# testboard_chip1_package.net
KiCad netlist of a schematic drawn in Altium Designer
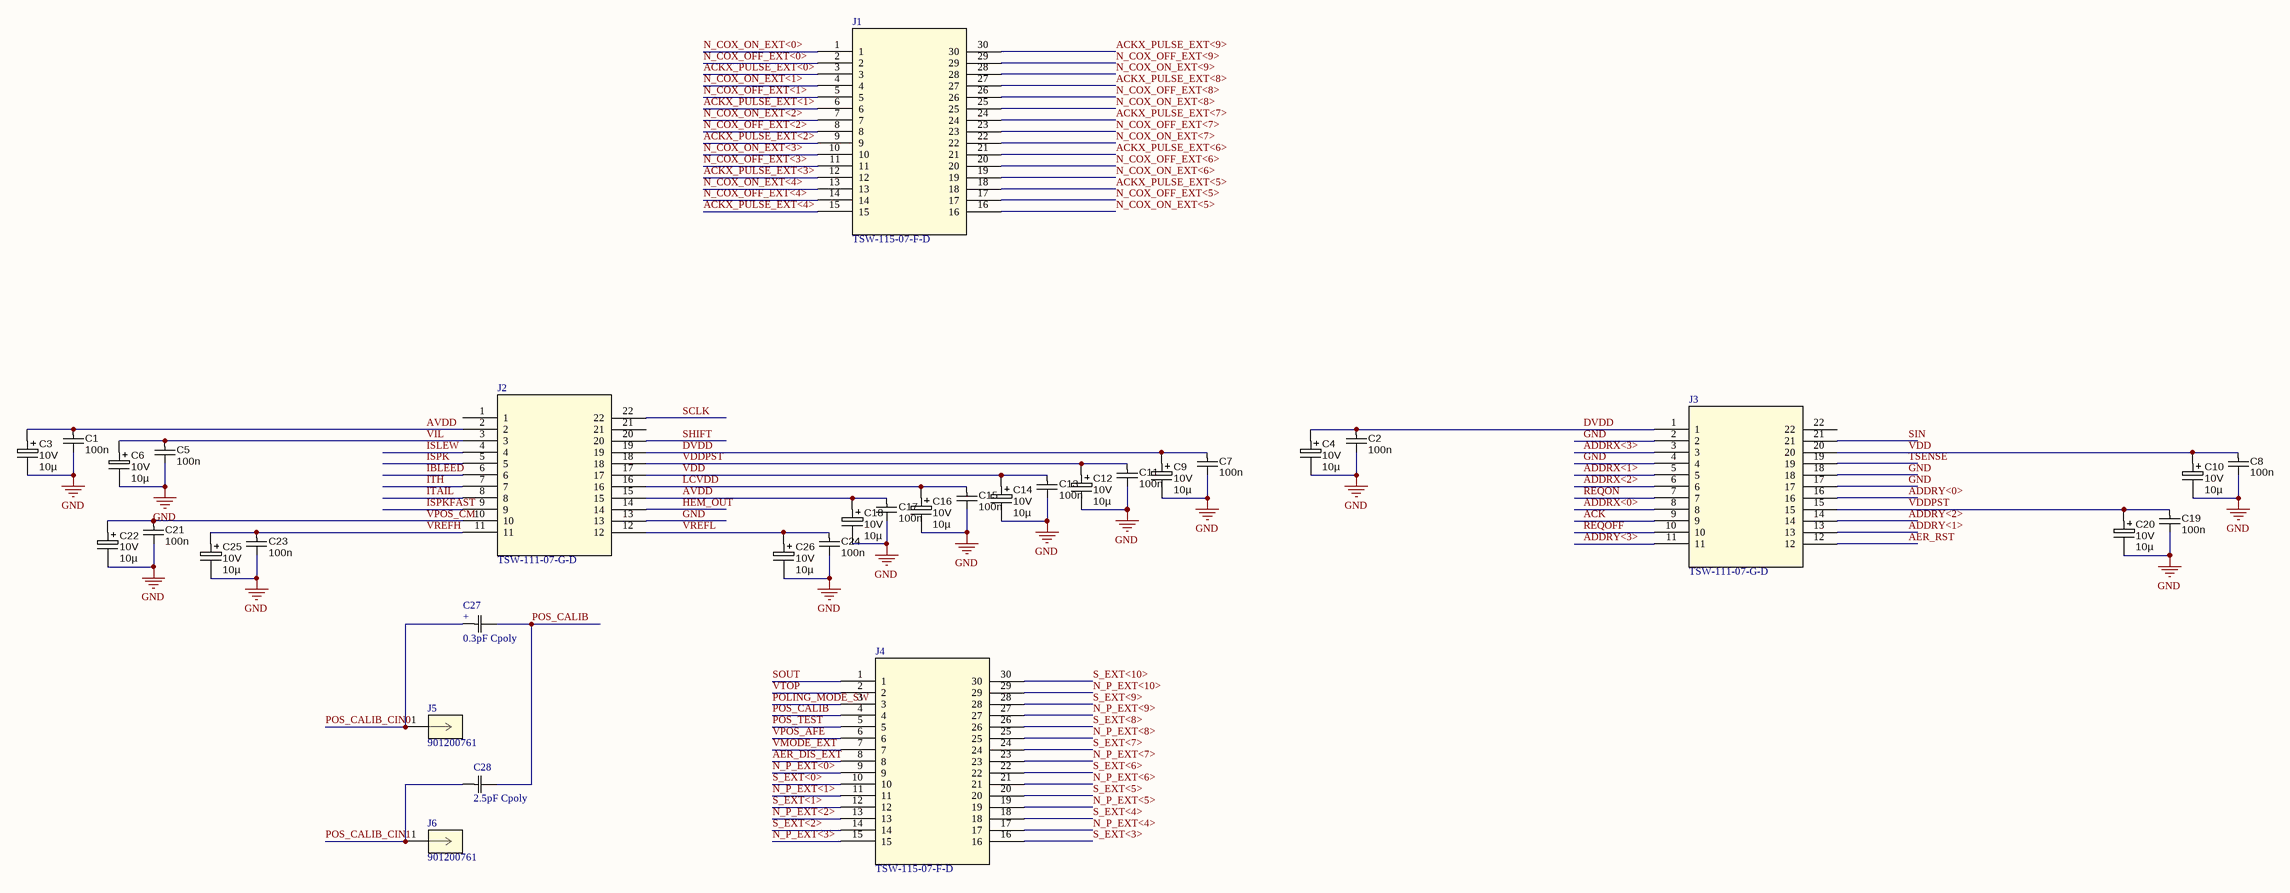
[diagram p0: testboard_chip1_package.SchDoc]

(export (version "E")
  (design (tool "Eeschema 10.0.6"))
  (components
    (comp (ref "C1")
      (value "100n")
      (footprint "CAPC1608N")
      (description "Capacitor SMD Cer 100nF 10% 50V X7R 0603")
      (fields (field (name "TOLERANCE") "±10%") (field (name "Comment") "approved sub OK"))
      (libsource (lib "PBL - Capacitors") (part "CAPC_100n_0603"))
    )
    (comp (ref "C2")
      (value "100n")
      (footprint "CAPC1608N")
      (description "Capacitor SMD Cer 100nF 10% 50V X7R 0603")
      (fields (field (name "TOLERANCE") "±10%") (field (name "Comment") "approved sub OK"))
      (libsource (lib "PBL - Capacitors") (part "CAPC_100n_0603"))
    )
    (comp (ref "C3")
      (value "10µ")
      (footprint "CAPMP2012X150USR")
      (description "Capacitor SMD Tantalum 10uF 20% 10V 0805")
      (fields (field (name "TOLERANCE") "±20%") (field (name "RATINGS") "10V"))
      (libsource (lib "PBL - Capacitors") (part "CAPT_10u_0805_10V"))
    )
    (comp (ref "C4")
      (value "10µ")
      (footprint "CAPMP2012X150USR")
      (description "Capacitor SMD Tantalum 10uF 20% 10V 0805")
      (fields (field (name "TOLERANCE") "±20%") (field (name "RATINGS") "10V"))
      (libsource (lib "PBL - Capacitors") (part "CAPT_10u_0805_10V"))
    )
    (comp (ref "C5")
      (value "100n")
      (footprint "CAPC1608N")
      (description "Capacitor SMD Cer 100nF 10% 50V X7R 0603")
      (fields (field (name "TOLERANCE") "±10%") (field (name "Comment") "approved sub OK"))
      (libsource (lib "PBL - Capacitors") (part "CAPC_100n_0603"))
    )
    (comp (ref "C6")
      (value "10µ")
      (footprint "CAPMP2012X150USR")
      (description "Capacitor SMD Tantalum 10uF 20% 10V 0805")
      (fields (field (name "TOLERANCE") "±20%") (field (name "RATINGS") "10V"))
      (libsource (lib "PBL - Capacitors") (part "CAPT_10u_0805_10V"))
    )
    (comp (ref "C7")
      (value "100n")
      (footprint "CAPC1608N")
      (description "Capacitor SMD Cer 100nF 10% 50V X7R 0603")
      (fields (field (name "TOLERANCE") "±10%") (field (name "Comment") "approved sub OK"))
      (libsource (lib "PBL - Capacitors") (part "CAPC_100n_0603"))
    )
    (comp (ref "C8")
      (value "100n")
      (footprint "CAPC1608N")
      (description "Capacitor SMD Cer 100nF 10% 50V X7R 0603")
      (fields (field (name "TOLERANCE") "±10%") (field (name "Comment") "approved sub OK"))
      (libsource (lib "PBL - Capacitors") (part "CAPC_100n_0603"))
    )
    (comp (ref "C9")
      (value "10µ")
      (footprint "CAPMP2012X150USR")
      (description "Capacitor SMD Tantalum 10uF 20% 10V 0805")
      (fields (field (name "TOLERANCE") "±20%") (field (name "RATINGS") "10V"))
      (libsource (lib "PBL - Capacitors") (part "CAPT_10u_0805_10V"))
    )
    (comp (ref "C10")
      (value "10µ")
      (footprint "CAPMP2012X150USR")
      (description "Capacitor SMD Tantalum 10uF 20% 10V 0805")
      (fields (field (name "TOLERANCE") "±20%") (field (name "RATINGS") "10V"))
      (libsource (lib "PBL - Capacitors") (part "CAPT_10u_0805_10V"))
    )
    (comp (ref "C11")
      (value "100n")
      (footprint "CAPC1608N")
      (description "Capacitor SMD Cer 100nF 10% 50V X7R 0603")
      (fields (field (name "TOLERANCE") "±10%") (field (name "Comment") "approved sub OK"))
      (libsource (lib "PBL - Capacitors") (part "CAPC_100n_0603"))
    )
    (comp (ref "C12")
      (value "10µ")
      (footprint "CAPMP2012X150USR")
      (description "Capacitor SMD Tantalum 10uF 20% 10V 0805")
      (fields (field (name "TOLERANCE") "±20%") (field (name "RATINGS") "10V"))
      (libsource (lib "PBL - Capacitors") (part "CAPT_10u_0805_10V"))
    )
    (comp (ref "C13")
      (value "100n")
      (footprint "CAPC1608N")
      (description "Capacitor SMD Cer 100nF 10% 50V X7R 0603")
      (fields (field (name "TOLERANCE") "±10%") (field (name "Comment") "approved sub OK"))
      (libsource (lib "PBL - Capacitors") (part "CAPC_100n_0603"))
    )
    (comp (ref "C14")
      (value "10µ")
      (footprint "CAPMP2012X150USR")
      (description "Capacitor SMD Tantalum 10uF 20% 10V 0805")
      (fields (field (name "TOLERANCE") "±20%") (field (name "RATINGS") "10V"))
      (libsource (lib "PBL - Capacitors") (part "CAPT_10u_0805_10V"))
    )
    (comp (ref "C15")
      (value "100n")
      (footprint "CAPC1608N")
      (description "Capacitor SMD Cer 100nF 10% 50V X7R 0603")
      (fields (field (name "TOLERANCE") "±10%") (field (name "Comment") "approved sub OK"))
      (libsource (lib "PBL - Capacitors") (part "CAPC_100n_0603"))
    )
    (comp (ref "C16")
      (value "10µ")
      (footprint "CAPMP2012X150USR")
      (description "Capacitor SMD Tantalum 10uF 20% 10V 0805")
      (fields (field (name "TOLERANCE") "±20%") (field (name "RATINGS") "10V"))
      (libsource (lib "PBL - Capacitors") (part "CAPT_10u_0805_10V"))
    )
    (comp (ref "C17")
      (value "100n")
      (footprint "CAPC1608N")
      (description "Capacitor SMD Cer 100nF 10% 50V X7R 0603")
      (fields (field (name "TOLERANCE") "±10%") (field (name "Comment") "approved sub OK"))
      (libsource (lib "PBL - Capacitors") (part "CAPC_100n_0603"))
    )
    (comp (ref "C18")
      (value "10µ")
      (footprint "CAPMP2012X150USR")
      (description "Capacitor SMD Tantalum 10uF 20% 10V 0805")
      (fields (field (name "TOLERANCE") "±20%") (field (name "RATINGS") "10V"))
      (libsource (lib "PBL - Capacitors") (part "CAPT_10u_0805_10V"))
    )
    (comp (ref "C19")
      (value "100n")
      (footprint "CAPC1608N")
      (description "Capacitor SMD Cer 100nF 10% 50V X7R 0603")
      (fields (field (name "TOLERANCE") "±10%") (field (name "Comment") "approved sub OK"))
      (libsource (lib "PBL - Capacitors") (part "CAPC_100n_0603"))
    )
    (comp (ref "C20")
      (value "10µ")
      (footprint "CAPMP2012X150USR")
      (description "Capacitor SMD Tantalum 10uF 20% 10V 0805")
      (fields (field (name "TOLERANCE") "±20%") (field (name "RATINGS") "10V"))
      (libsource (lib "PBL - Capacitors") (part "CAPT_10u_0805_10V"))
    )
    (comp (ref "C21")
      (value "100n")
      (footprint "CAPC1608N")
      (description "Capacitor SMD Cer 100nF 10% 50V X7R 0603")
      (fields (field (name "TOLERANCE") "±10%") (field (name "Comment") "approved sub OK"))
      (libsource (lib "PBL - Capacitors") (part "CAPC_100n_0603"))
    )
    (comp (ref "C22")
      (value "10µ")
      (footprint "CAPMP2012X150USR")
      (description "Capacitor SMD Tantalum 10uF 20% 10V 0805")
      (fields (field (name "TOLERANCE") "±20%") (field (name "RATINGS") "10V"))
      (libsource (lib "PBL - Capacitors") (part "CAPT_10u_0805_10V"))
    )
    (comp (ref "C23")
      (value "100n")
      (footprint "CAPC1608N")
      (description "Capacitor SMD Cer 100nF 10% 50V X7R 0603")
      (fields (field (name "TOLERANCE") "±10%") (field (name "Comment") "approved sub OK"))
      (libsource (lib "PBL - Capacitors") (part "CAPC_100n_0603"))
    )
    (comp (ref "C24")
      (value "100n")
      (footprint "CAPC1608N")
      (description "Capacitor SMD Cer 100nF 10% 50V X7R 0603")
      (fields (field (name "TOLERANCE") "±10%") (field (name "Comment") "approved sub OK"))
      (libsource (lib "PBL - Capacitors") (part "CAPC_100n_0603"))
    )
    (comp (ref "C25")
      (value "10µ")
      (footprint "CAPMP2012X150USR")
      (description "Capacitor SMD Tantalum 10uF 20% 10V 0805")
      (fields (field (name "TOLERANCE") "±20%") (field (name "RATINGS") "10V"))
      (libsource (lib "PBL - Capacitors") (part "CAPT_10u_0805_10V"))
    )
    (comp (ref "C26")
      (value "10µ")
      (footprint "CAPMP2012X150USR")
      (description "Capacitor SMD Tantalum 10uF 20% 10V 0805")
      (fields (field (name "TOLERANCE") "±20%") (field (name "RATINGS") "10V"))
      (libsource (lib "PBL - Capacitors") (part "CAPT_10u_0805_10V"))
    )
    (comp (ref "C27")
      (value "0.3pF Cpoly")
      (footprint "CAP_0603_AVX")
      (description "No Description Available")
      (fields
        (field (name "MANUFACTURER_PART_NUMBER") "06035J0R3PBSTR")
        (field (name "COPYRIGHT") "Copyright (C) 2022 Ultra Librarian. All rights reserved.")
      )
      (libsource (lib "06035J0R3PBSTR") (part "06035J0R3PBSTR"))
    )
    (comp (ref "C28")
      (value "2.5pF Cpoly")
      (footprint "CAPC17090_87N_KEM")
      (description "No Description Available")
      (fields
        (field (name "MANUFACTURER_PART_NUMBER") "CBR06C259B5GAC")
        (field (name "COPYRIGHT") "Copyright (C) 2022 Ultra Librarian. All rights reserved.")
      )
      (libsource (lib "CBR06C259B5GAC") (part "CBR06C259B5GAC"))
    )
    (comp (ref "J1")
      (value "TSW-115-07-F-D")
      (footprint "TSW-115-07-G-D_SAI")
      (description "No Description Available")
      (fields (field (name "COPYRIGHT") "Copyright (C) 2022 Ultra Librarian. All rights reserved."))
      (libsource (lib "TSW-115-07-F-D") (part "TSW-115-07-F-D"))
    )
    (comp (ref "J2")
      (value "TSW-111-07-G-D")
      (footprint "TSW-111-07-G-D_SAI")
      (description "No Description Available")
      (fields (field (name "COPYRIGHT") "Copyright (C) 2022 Ultra Librarian. All rights reserved."))
      (libsource (lib "TSW-111-07-G-D") (part "TSW-111-07-G-D"))
    )
    (comp (ref "J3")
      (value "TSW-111-07-G-D")
      (footprint "TSW-111-07-G-D_SAI")
      (description "No Description Available")
      (fields (field (name "COPYRIGHT") "Copyright (C) 2022 Ultra Librarian. All rights reserved."))
      (libsource (lib "TSW-111-07-G-D") (part "TSW-111-07-G-D"))
    )
    (comp (ref "J4")
      (value "TSW-115-07-F-D")
      (footprint "TSW-115-07-G-D_SAI")
      (description "No Description Available")
      (fields (field (name "COPYRIGHT") "Copyright (C) 2022 Ultra Librarian. All rights reserved."))
      (libsource (lib "TSW-115-07-F-D") (part "TSW-115-07-F-D"))
    )
    (comp (ref "J5")
      (value "901200761")
      (footprint "CONN_90120-0761_MOL")
      (description "No Description Available")
      (fields (field (name "COPYRIGHT") "Copyright (C) 2022 Ultra Librarian. All rights reserved."))
      (libsource (lib "901200761") (part "901200761"))
    )
    (comp (ref "J6")
      (value "901200761")
      (footprint "CONN_90120-0761_MOL")
      (description "No Description Available")
      (fields (field (name "COPYRIGHT") "Copyright (C) 2022 Ultra Librarian. All rights reserved."))
      (libsource (lib "901200761") (part "901200761"))
    )
  )
  (nets
    (net (code "1") (name "/ACK") (class "Default")
      (node (ref "J3") (pin "9") (pinfunction "9_9") (pintype "passive"))
    )
    (net (code "2") (name "/ACKX_PULSE_EXT<0>") (class "Default")
      (node (ref "J1") (pin "3") (pinfunction "3_3") (pintype "passive"))
    )
    (net (code "3") (name "/ACKX_PULSE_EXT<1>") (class "Default")
      (node (ref "J1") (pin "6") (pinfunction "6_6") (pintype "passive"))
    )
    (net (code "4") (name "/ACKX_PULSE_EXT<2>") (class "Default")
      (node (ref "J1") (pin "9") (pinfunction "9_9") (pintype "passive"))
    )
    (net (code "5") (name "/ACKX_PULSE_EXT<3>") (class "Default")
      (node (ref "J1") (pin "12") (pinfunction "12_12") (pintype "passive"))
    )
    (net (code "6") (name "/ACKX_PULSE_EXT<4>") (class "Default")
      (node (ref "J1") (pin "15") (pinfunction "15_15") (pintype "passive"))
    )
    (net (code "7") (name "/ACKX_PULSE_EXT<5>") (class "Default")
      (node (ref "J1") (pin "18") (pinfunction "18_18") (pintype "passive"))
    )
    (net (code "8") (name "/ACKX_PULSE_EXT<6>") (class "Default")
      (node (ref "J1") (pin "21") (pinfunction "21_21") (pintype "passive"))
    )
    (net (code "9") (name "/ACKX_PULSE_EXT<7>") (class "Default")
      (node (ref "J1") (pin "24") (pinfunction "24_24") (pintype "passive"))
    )
    (net (code "10") (name "/ACKX_PULSE_EXT<8>") (class "Default")
      (node (ref "J1") (pin "27") (pinfunction "27_27") (pintype "passive"))
    )
    (net (code "11") (name "/ACKX_PULSE_EXT<9>") (class "Default")
      (node (ref "J1") (pin "30") (pinfunction "30_30") (pintype "passive"))
    )
    (net (code "12") (name "/ADDRX<0>") (class "Default")
      (node (ref "J3") (pin "8") (pinfunction "8_8") (pintype "passive"))
    )
    (net (code "13") (name "/ADDRX<1>") (class "Default")
      (node (ref "J3") (pin "5") (pinfunction "5_5") (pintype "passive"))
    )
    (net (code "14") (name "/ADDRX<2>") (class "Default")
      (node (ref "J3") (pin "6") (pinfunction "6_6") (pintype "passive"))
    )
    (net (code "15") (name "/ADDRX<3>") (class "Default")
      (node (ref "J3") (pin "3") (pinfunction "3_3") (pintype "passive"))
    )
    (net (code "16") (name "/ADDRY<0>") (class "Default")
      (node (ref "J3") (pin "16") (pinfunction "16_16") (pintype "passive"))
    )
    (net (code "17") (name "/ADDRY<1>") (class "Default")
      (node (ref "J3") (pin "13") (pinfunction "13_13") (pintype "passive"))
    )
    (net (code "18") (name "/ADDRY<2>") (class "Default")
      (node (ref "J3") (pin "14") (pinfunction "14_14") (pintype "passive"))
    )
    (net (code "19") (name "/ADDRY<3>") (class "Default")
      (node (ref "J3") (pin "11") (pinfunction "11_11") (pintype "passive"))
    )
    (net (code "20") (name "/AER_DIS_EXT") (class "Default")
      (node (ref "J4") (pin "8") (pinfunction "8_8") (pintype "passive"))
    )
    (net (code "21") (name "/AER_RST") (class "Default")
      (node (ref "J3") (pin "12") (pinfunction "12_12") (pintype "passive"))
    )
    (net (code "22") (name "/AVDD") (class "Default")
      (node (ref "C1") (pin "1") (pintype "passive"))
      (node (ref "C17") (pin "1") (pintype "passive"))
      (node (ref "C18") (pin "1") (pintype "passive"))
      (node (ref "C3") (pin "1") (pintype "passive"))
      (node (ref "J2") (pin "15") (pinfunction "15_15") (pintype "passive"))
      (node (ref "J2") (pin "2") (pinfunction "2_2") (pintype "passive"))
    )
    (net (code "23") (name "/DVDD") (class "Default")
      (node (ref "C2") (pin "1") (pintype "passive"))
      (node (ref "C4") (pin "1") (pintype "passive"))
      (node (ref "C7") (pin "1") (pintype "passive"))
      (node (ref "C9") (pin "1") (pintype "passive"))
      (node (ref "J2") (pin "19") (pinfunction "19_19") (pintype "passive"))
      (node (ref "J3") (pin "1") (pinfunction "1_1") (pintype "passive"))
    )
    (net (code "24") (name "/HEM_OUT") (class "Default")
      (node (ref "J2") (pin "14") (pinfunction "14_14") (pintype "passive"))
    )
    (net (code "25") (name "/IBLEED") (class "Default")
      (node (ref "J2") (pin "6") (pinfunction "6_6") (pintype "passive"))
    )
    (net (code "26") (name "/ISLEW") (class "Default")
      (node (ref "J2") (pin "4") (pinfunction "4_4") (pintype "passive"))
    )
    (net (code "27") (name "/ISPK") (class "Default")
      (node (ref "J2") (pin "5") (pinfunction "5_5") (pintype "passive"))
    )
    (net (code "28") (name "/ISPKFAST") (class "Default")
      (node (ref "J2") (pin "9") (pinfunction "9_9") (pintype "passive"))
    )
    (net (code "29") (name "/ITAIL") (class "Default")
      (node (ref "J2") (pin "8") (pinfunction "8_8") (pintype "passive"))
    )
    (net (code "30") (name "/ITH") (class "Default")
      (node (ref "J2") (pin "7") (pinfunction "7_7") (pintype "passive"))
    )
    (net (code "31") (name "/LCVDD") (class "Default")
      (node (ref "C15") (pin "1") (pintype "passive"))
      (node (ref "C16") (pin "1") (pintype "passive"))
      (node (ref "J2") (pin "16") (pinfunction "16_16") (pintype "passive"))
    )
    (net (code "32") (name "/N_COX_OFF_EXT<0>") (class "Default")
      (node (ref "J1") (pin "2") (pinfunction "2_2") (pintype "passive"))
    )
    (net (code "33") (name "/N_COX_OFF_EXT<1>") (class "Default")
      (node (ref "J1") (pin "5") (pinfunction "5_5") (pintype "passive"))
    )
    (net (code "34") (name "/N_COX_OFF_EXT<2>") (class "Default")
      (node (ref "J1") (pin "8") (pinfunction "8_8") (pintype "passive"))
    )
    (net (code "35") (name "/N_COX_OFF_EXT<3>") (class "Default")
      (node (ref "J1") (pin "11") (pinfunction "11_11") (pintype "passive"))
    )
    (net (code "36") (name "/N_COX_OFF_EXT<4>") (class "Default")
      (node (ref "J1") (pin "14") (pinfunction "14_14") (pintype "passive"))
    )
    (net (code "37") (name "/N_COX_OFF_EXT<5>") (class "Default")
      (node (ref "J1") (pin "17") (pinfunction "17_17") (pintype "passive"))
    )
    (net (code "38") (name "/N_COX_OFF_EXT<6>") (class "Default")
      (node (ref "J1") (pin "20") (pinfunction "20_20") (pintype "passive"))
    )
    (net (code "39") (name "/N_COX_OFF_EXT<7>") (class "Default")
      (node (ref "J1") (pin "23") (pinfunction "23_23") (pintype "passive"))
    )
    (net (code "40") (name "/N_COX_OFF_EXT<8>") (class "Default")
      (node (ref "J1") (pin "26") (pinfunction "26_26") (pintype "passive"))
    )
    (net (code "41") (name "/N_COX_OFF_EXT<9>") (class "Default")
      (node (ref "J1") (pin "29") (pinfunction "29_29") (pintype "passive"))
    )
    (net (code "42") (name "/N_COX_ON_EXT<0>") (class "Default")
      (node (ref "J1") (pin "1") (pinfunction "1_1") (pintype "passive"))
    )
    (net (code "43") (name "/N_COX_ON_EXT<1>") (class "Default")
      (node (ref "J1") (pin "4") (pinfunction "4_4") (pintype "passive"))
    )
    (net (code "44") (name "/N_COX_ON_EXT<2>") (class "Default")
      (node (ref "J1") (pin "7") (pinfunction "7_7") (pintype "passive"))
    )
    (net (code "45") (name "/N_COX_ON_EXT<3>") (class "Default")
      (node (ref "J1") (pin "10") (pinfunction "10_10") (pintype "passive"))
    )
    (net (code "46") (name "/N_COX_ON_EXT<4>") (class "Default")
      (node (ref "J1") (pin "13") (pinfunction "13_13") (pintype "passive"))
    )
    (net (code "47") (name "/N_COX_ON_EXT<5>") (class "Default")
      (node (ref "J1") (pin "16") (pinfunction "16_16") (pintype "passive"))
    )
    (net (code "48") (name "/N_COX_ON_EXT<6>") (class "Default")
      (node (ref "J1") (pin "19") (pinfunction "19_19") (pintype "passive"))
    )
    (net (code "49") (name "/N_COX_ON_EXT<7>") (class "Default")
      (node (ref "J1") (pin "22") (pinfunction "22_22") (pintype "passive"))
    )
    (net (code "50") (name "/N_COX_ON_EXT<8>") (class "Default")
      (node (ref "J1") (pin "25") (pinfunction "25_25") (pintype "passive"))
    )
    (net (code "51") (name "/N_COX_ON_EXT<9>") (class "Default")
      (node (ref "J1") (pin "28") (pinfunction "28_28") (pintype "passive"))
    )
    (net (code "52") (name "/N_P_EXT<0>") (class "Default")
      (node (ref "J4") (pin "9") (pinfunction "9_9") (pintype "passive"))
    )
    (net (code "53") (name "/N_P_EXT<1>") (class "Default")
      (node (ref "J4") (pin "11") (pinfunction "11_11") (pintype "passive"))
    )
    (net (code "54") (name "/N_P_EXT<2>") (class "Default")
      (node (ref "J4") (pin "13") (pinfunction "13_13") (pintype "passive"))
    )
    (net (code "55") (name "/N_P_EXT<3>") (class "Default")
      (node (ref "J4") (pin "15") (pinfunction "15_15") (pintype "passive"))
    )
    (net (code "56") (name "/N_P_EXT<4>") (class "Default")
      (node (ref "J4") (pin "17") (pinfunction "17_17") (pintype "passive"))
    )
    (net (code "57") (name "/N_P_EXT<5>") (class "Default")
      (node (ref "J4") (pin "19") (pinfunction "19_19") (pintype "passive"))
    )
    (net (code "58") (name "/N_P_EXT<6>") (class "Default")
      (node (ref "J4") (pin "21") (pinfunction "21_21") (pintype "passive"))
    )
    (net (code "59") (name "/N_P_EXT<7>") (class "Default")
      (node (ref "J4") (pin "23") (pinfunction "23_23") (pintype "passive"))
    )
    (net (code "60") (name "/N_P_EXT<8>") (class "Default")
      (node (ref "J4") (pin "25") (pinfunction "25_25") (pintype "passive"))
    )
    (net (code "61") (name "/N_P_EXT<9>") (class "Default")
      (node (ref "J4") (pin "27") (pinfunction "27_27") (pintype "passive"))
    )
    (net (code "62") (name "/N_P_EXT<10>") (class "Default")
      (node (ref "J4") (pin "29") (pinfunction "29_29") (pintype "passive"))
    )
    (net (code "63") (name "/POLING_MODE_SW") (class "Default")
      (node (ref "J4") (pin "3") (pinfunction "3_3") (pintype "passive"))
    )
    (net (code "64") (name "/POS_CALIB") (class "Default")
      (node (ref "C27") (pin "2") (pinfunction "2_2") (pintype "passive"))
      (node (ref "C28") (pin "2") (pinfunction "2_2") (pintype "passive"))
      (node (ref "J4") (pin "4") (pinfunction "4_4") (pintype "passive"))
    )
    (net (code "65") (name "/POS_CALIB_CIN0") (class "Default")
      (node (ref "C27") (pin "1") (pinfunction "1_1") (pintype "passive"))
      (node (ref "J5") (pin "1") (pinfunction "1_1") (pintype "passive"))
    )
    (net (code "66") (name "/POS_CALIB_CIN1") (class "Default")
      (node (ref "C28") (pin "1") (pinfunction "1_1") (pintype "passive"))
      (node (ref "J6") (pin "1") (pinfunction "1_1") (pintype "passive"))
    )
    (net (code "67") (name "/POS_TEST") (class "Default")
      (node (ref "J4") (pin "5") (pinfunction "5_5") (pintype "passive"))
    )
    (net (code "68") (name "/REQOFF") (class "Default")
      (node (ref "J3") (pin "10") (pinfunction "10_10") (pintype "passive"))
    )
    (net (code "69") (name "/REQON") (class "Default")
      (node (ref "J3") (pin "7") (pinfunction "7_7") (pintype "passive"))
    )
    (net (code "70") (name "/SCLK") (class "Default")
      (node (ref "J2") (pin "22") (pinfunction "22_22") (pintype "passive"))
    )
    (net (code "71") (name "/SHIFT") (class "Default")
      (node (ref "J2") (pin "20") (pinfunction "20_20") (pintype "passive"))
    )
    (net (code "72") (name "/SIN") (class "Default")
      (node (ref "J3") (pin "21") (pinfunction "21_21") (pintype "passive"))
    )
    (net (code "73") (name "/SOUT") (class "Default")
      (node (ref "J4") (pin "1") (pinfunction "1_1") (pintype "passive"))
    )
    (net (code "74") (name "/S_EXT<0>") (class "Default")
      (node (ref "J4") (pin "10") (pinfunction "10_10") (pintype "passive"))
    )
    (net (code "75") (name "/S_EXT<1>") (class "Default")
      (node (ref "J4") (pin "12") (pinfunction "12_12") (pintype "passive"))
    )
    (net (code "76") (name "/S_EXT<2>") (class "Default")
      (node (ref "J4") (pin "14") (pinfunction "14_14") (pintype "passive"))
    )
    (net (code "77") (name "/S_EXT<3>") (class "Default")
      (node (ref "J4") (pin "16") (pinfunction "16_16") (pintype "passive"))
    )
    (net (code "78") (name "/S_EXT<4>") (class "Default")
      (node (ref "J4") (pin "18") (pinfunction "18_18") (pintype "passive"))
    )
    (net (code "79") (name "/S_EXT<5>") (class "Default")
      (node (ref "J4") (pin "20") (pinfunction "20_20") (pintype "passive"))
    )
    (net (code "80") (name "/S_EXT<6>") (class "Default")
      (node (ref "J4") (pin "22") (pinfunction "22_22") (pintype "passive"))
    )
    (net (code "81") (name "/S_EXT<7>") (class "Default")
      (node (ref "J4") (pin "24") (pinfunction "24_24") (pintype "passive"))
    )
    (net (code "82") (name "/S_EXT<8>") (class "Default")
      (node (ref "J4") (pin "26") (pinfunction "26_26") (pintype "passive"))
    )
    (net (code "83") (name "/S_EXT<9>") (class "Default")
      (node (ref "J4") (pin "28") (pinfunction "28_28") (pintype "passive"))
    )
    (net (code "84") (name "/S_EXT<10>") (class "Default")
      (node (ref "J4") (pin "30") (pinfunction "30_30") (pintype "passive"))
    )
    (net (code "85") (name "/TSENSE") (class "Default")
      (node (ref "J3") (pin "19") (pinfunction "19_19") (pintype "passive"))
    )
    (net (code "86") (name "/VDD") (class "Default")
      (node (ref "C10") (pin "1") (pintype "passive"))
      (node (ref "C13") (pin "1") (pintype "passive"))
      (node (ref "C14") (pin "1") (pintype "passive"))
      (node (ref "C8") (pin "1") (pintype "passive"))
      (node (ref "J2") (pin "17") (pinfunction "17_17") (pintype "passive"))
      (node (ref "J3") (pin "20") (pinfunction "20_20") (pintype "passive"))
    )
    (net (code "87") (name "/VDDPST") (class "Default")
      (node (ref "C11") (pin "1") (pintype "passive"))
      (node (ref "C12") (pin "1") (pintype "passive"))
      (node (ref "C19") (pin "1") (pintype "passive"))
      (node (ref "C20") (pin "1") (pintype "passive"))
      (node (ref "J2") (pin "18") (pinfunction "18_18") (pintype "passive"))
      (node (ref "J3") (pin "15") (pinfunction "15_15") (pintype "passive"))
    )
    (net (code "88") (name "/VIL") (class "Default")
      (node (ref "C5") (pin "1") (pintype "passive"))
      (node (ref "C6") (pin "1") (pintype "passive"))
      (node (ref "J2") (pin "3") (pinfunction "3_3") (pintype "passive"))
    )
    (net (code "89") (name "/VMODE_EXT") (class "Default")
      (node (ref "J4") (pin "7") (pinfunction "7_7") (pintype "passive"))
    )
    (net (code "90") (name "/VPOS_AFE") (class "Default")
      (node (ref "J4") (pin "6") (pinfunction "6_6") (pintype "passive"))
    )
    (net (code "91") (name "/VPOS_CM") (class "Default")
      (node (ref "C21") (pin "1") (pintype "passive"))
      (node (ref "C22") (pin "1") (pintype "passive"))
      (node (ref "J2") (pin "10") (pinfunction "10_10") (pintype "passive"))
    )
    (net (code "92") (name "/VREFH") (class "Default")
      (node (ref "C23") (pin "1") (pintype "passive"))
      (node (ref "C25") (pin "1") (pintype "passive"))
      (node (ref "J2") (pin "11") (pinfunction "11_11") (pintype "passive"))
    )
    (net (code "93") (name "/VREFL") (class "Default")
      (node (ref "C24") (pin "1") (pintype "passive"))
      (node (ref "C26") (pin "1") (pintype "passive"))
      (node (ref "J2") (pin "12") (pinfunction "12_12") (pintype "passive"))
    )
    (net (code "94") (name "/VTOP") (class "Default")
      (node (ref "J4") (pin "2") (pinfunction "2_2") (pintype "passive"))
    )
    (net (code "95") (name "GND") (class "Default")
      (node (ref "C1") (pin "2") (pintype "passive"))
      (node (ref "C10") (pin "2") (pintype "passive"))
      (node (ref "C11") (pin "2") (pintype "passive"))
      (node (ref "C12") (pin "2") (pintype "passive"))
      (node (ref "C13") (pin "2") (pintype "passive"))
      (node (ref "C14") (pin "2") (pintype "passive"))
      (node (ref "C15") (pin "2") (pintype "passive"))
      (node (ref "C16") (pin "2") (pintype "passive"))
      (node (ref "C17") (pin "2") (pintype "passive"))
      (node (ref "C18") (pin "2") (pintype "passive"))
      (node (ref "C19") (pin "2") (pintype "passive"))
      (node (ref "C2") (pin "2") (pintype "passive"))
      (node (ref "C20") (pin "2") (pintype "passive"))
      (node (ref "C21") (pin "2") (pintype "passive"))
      (node (ref "C22") (pin "2") (pintype "passive"))
      (node (ref "C23") (pin "2") (pintype "passive"))
      (node (ref "C24") (pin "2") (pintype "passive"))
      (node (ref "C25") (pin "2") (pintype "passive"))
      (node (ref "C26") (pin "2") (pintype "passive"))
      (node (ref "C3") (pin "2") (pintype "passive"))
      (node (ref "C4") (pin "2") (pintype "passive"))
      (node (ref "C5") (pin "2") (pintype "passive"))
      (node (ref "C6") (pin "2") (pintype "passive"))
      (node (ref "C7") (pin "2") (pintype "passive"))
      (node (ref "C8") (pin "2") (pintype "passive"))
      (node (ref "C9") (pin "2") (pintype "passive"))
      (node (ref "J2") (pin "13") (pinfunction "13_13") (pintype "passive"))
      (node (ref "J3") (pin "17") (pinfunction "17_17") (pintype "passive"))
      (node (ref "J3") (pin "18") (pinfunction "18_18") (pintype "passive"))
      (node (ref "J3") (pin "2") (pinfunction "2_2") (pintype "passive"))
      (node (ref "J3") (pin "4") (pinfunction "4_4") (pintype "passive"))
    )
    (net (code "96") (name "unconnected-(J2-Pad1)") (class "Default")
      (node (ref "J2") (pin "1") (pinfunction "1_1") (pintype "passive"))
    )
    (net (code "97") (name "unconnected-(J2-Pad21)") (class "Default")
      (node (ref "J2") (pin "21") (pinfunction "21_21") (pintype "passive"))
    )
    (net (code "98") (name "unconnected-(J3-Pad22)") (class "Default")
      (node (ref "J3") (pin "22") (pinfunction "22_22") (pintype "passive"))
    )
  )
)
